# oresat-batteries-v1_1.net
KiCad netlist of a schematic drawn in EAGLE
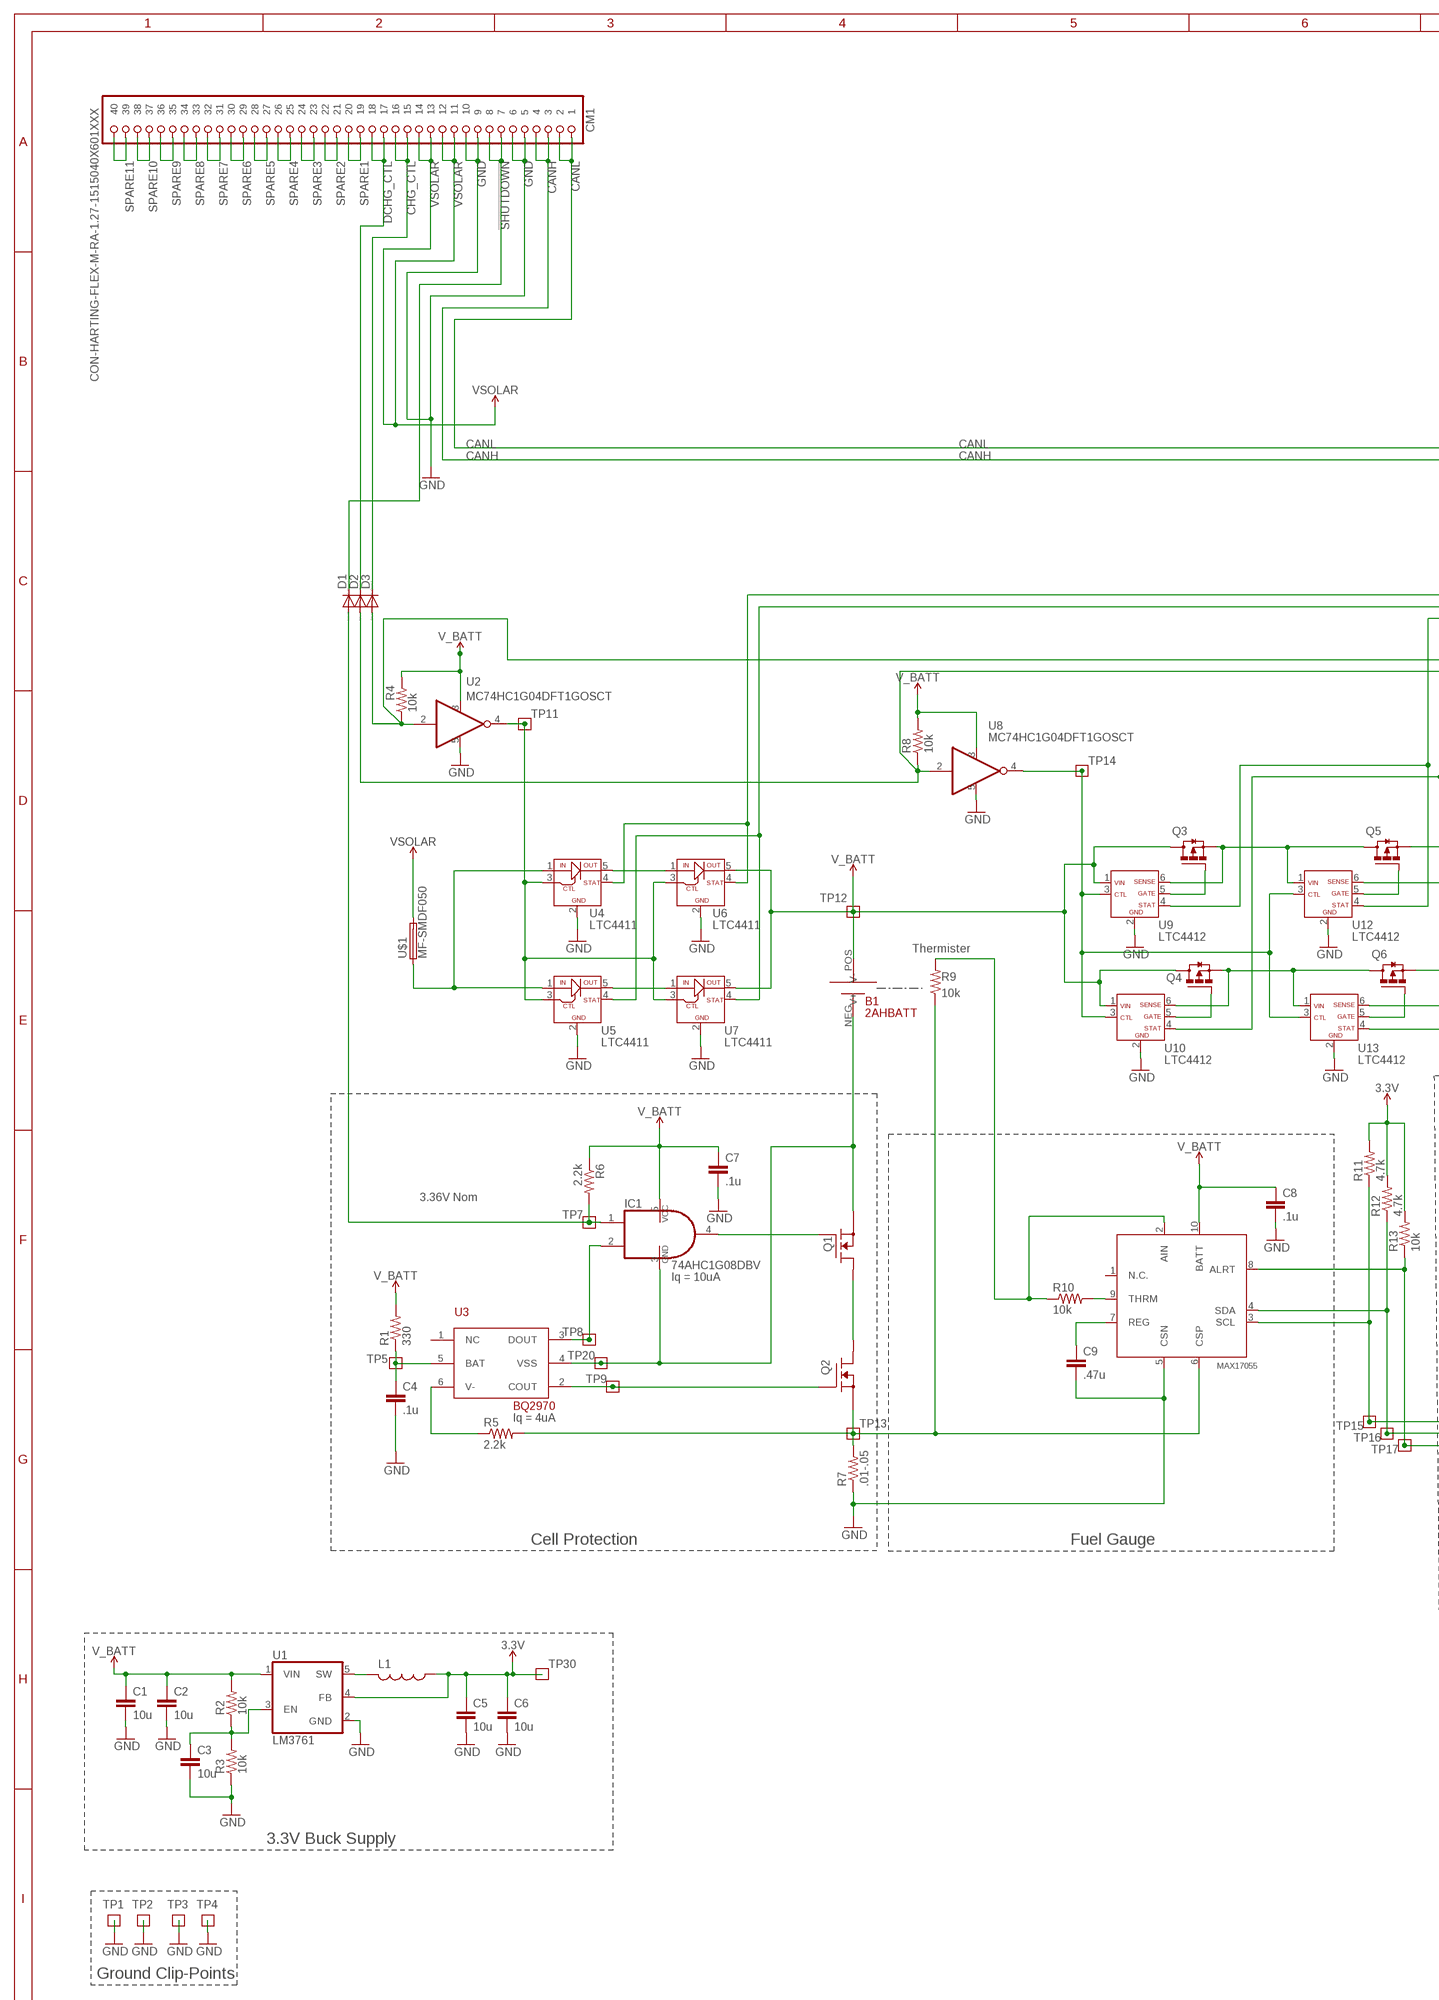
[diagram p0: schematic, sheet 1, part 1 of 2]
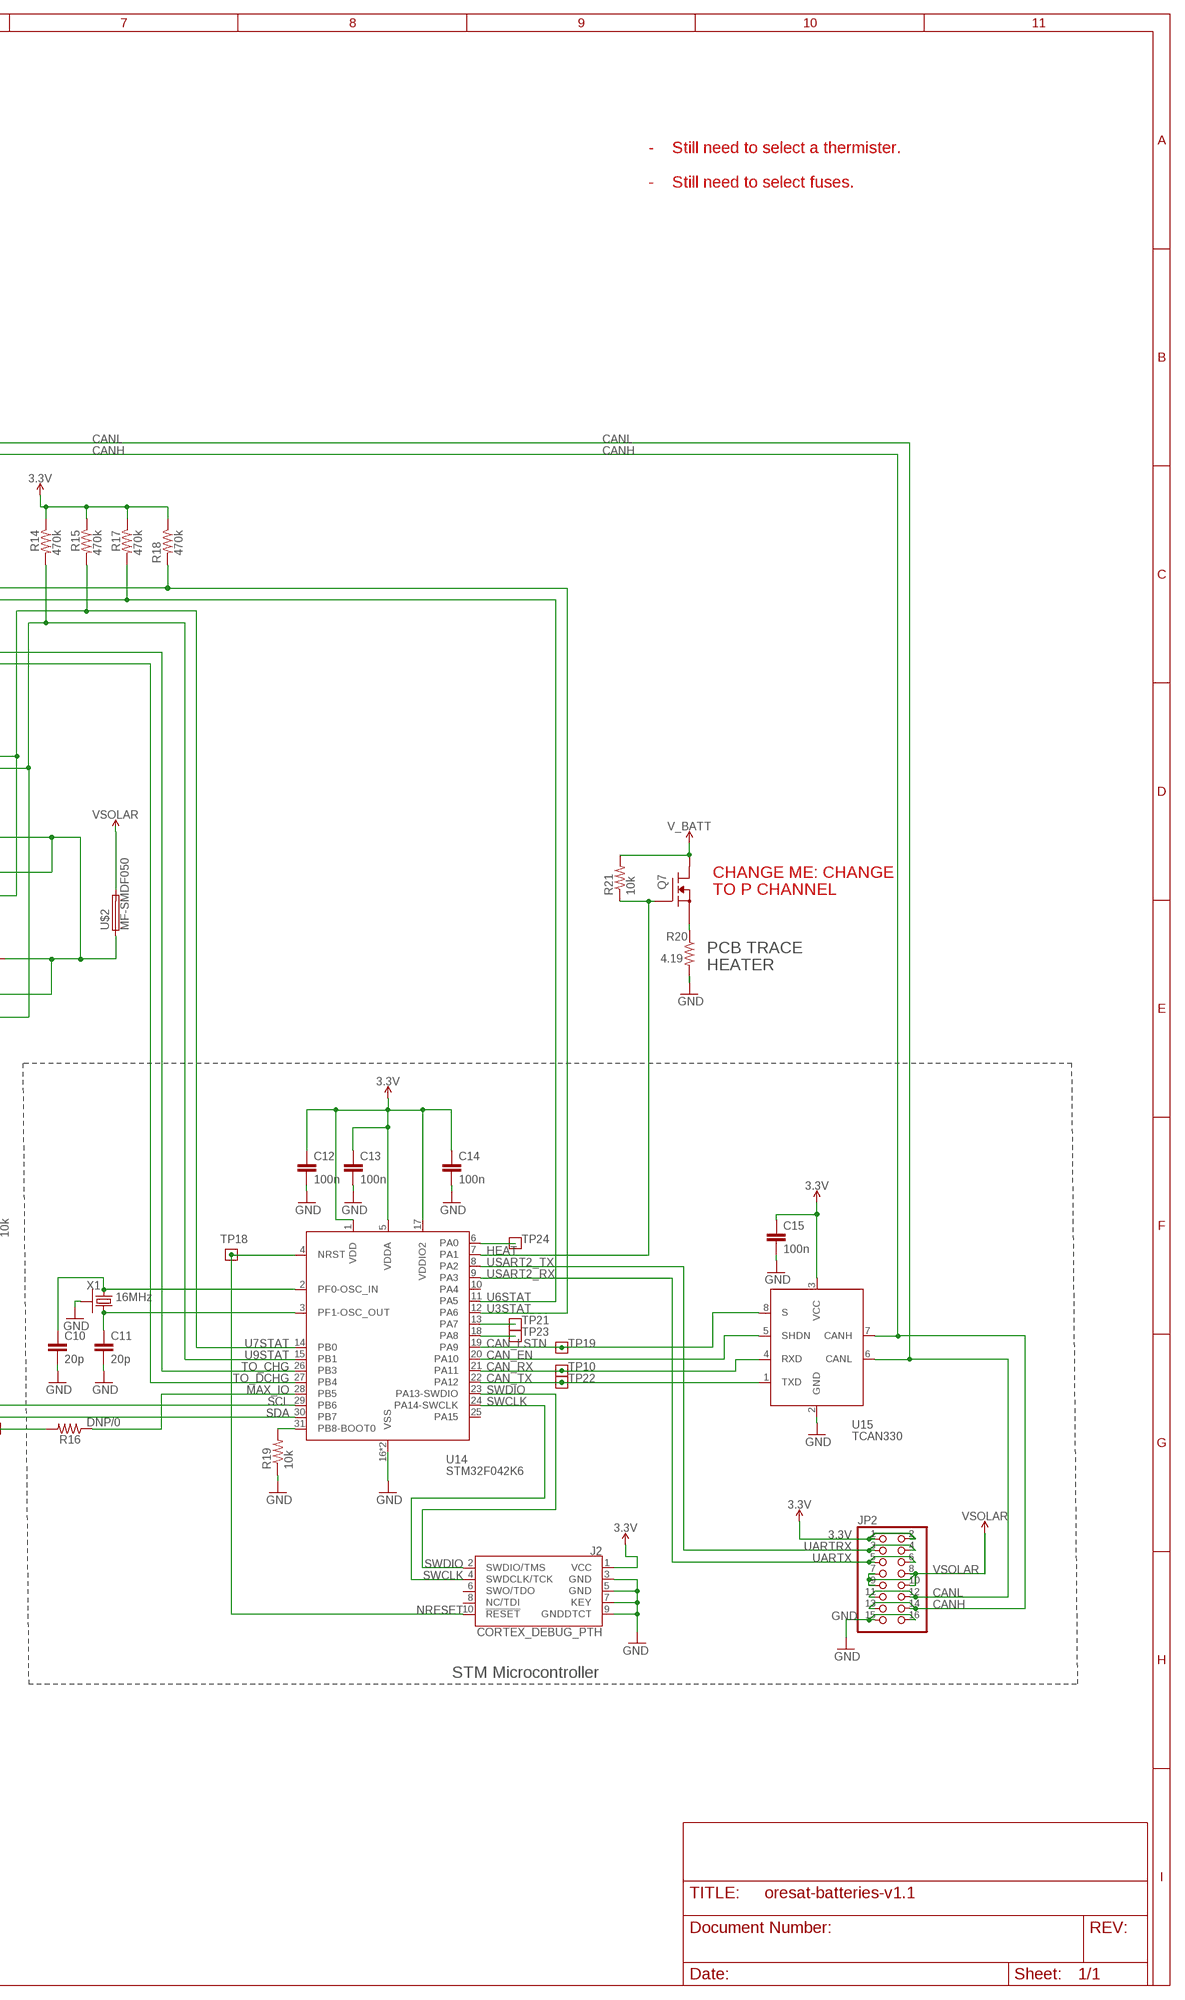
[diagram p1: schematic, sheet 1, part 2 of 2]

(export (version "E")
  (design (tool "Eeschema 10.0.6"))
  (components
    (comp (ref "B1")
      (value "2AHBATT")
      (footprint "eagle-import:2AH_605060")
      (libsource (lib "eagle-import") (part "2AHBATT"))
    )
    (comp (ref "C1")
      (value "10u")
      (footprint "eagle-import:C0805")
      (libsource (lib "eagle-import") (part "C-EUC0805"))
    )
    (comp (ref "C2")
      (value "10u")
      (footprint "eagle-import:C0805")
      (libsource (lib "eagle-import") (part "C-EUC0805"))
    )
    (comp (ref "C3")
      (value "10u")
      (footprint "eagle-import:C0805")
      (libsource (lib "eagle-import") (part "C-EUC0805"))
    )
    (comp (ref "C4")
      (value ".1u")
      (footprint "eagle-import:C0603")
      (libsource (lib "eagle-import") (part "C-EUC0603"))
    )
    (comp (ref "C5")
      (value "10u")
      (footprint "eagle-import:C0805")
      (libsource (lib "eagle-import") (part "C-EUC0805"))
    )
    (comp (ref "C6")
      (value "10u")
      (footprint "eagle-import:C0805")
      (libsource (lib "eagle-import") (part "C-EUC0805"))
    )
    (comp (ref "C7")
      (value ".1u")
      (footprint "eagle-import:C0603")
      (libsource (lib "eagle-import") (part "C-EUC0603"))
    )
    (comp (ref "C8")
      (value ".1u")
      (footprint "eagle-import:C0603")
      (libsource (lib "eagle-import") (part "C-EUC0603"))
    )
    (comp (ref "C9")
      (value ".47u")
      (footprint "eagle-import:C0603")
      (libsource (lib "eagle-import") (part "C-EUC0603"))
    )
    (comp (ref "C10")
      (value "20p")
      (footprint "eagle-import:C0603")
      (libsource (lib "eagle-import") (part "C-EUC0603"))
    )
    (comp (ref "C11")
      (value "20p")
      (footprint "eagle-import:C0603")
      (libsource (lib "eagle-import") (part "C-EUC0603"))
    )
    (comp (ref "C12")
      (value "100n")
      (footprint "eagle-import:C0603")
      (libsource (lib "eagle-import") (part "C-EUC0603"))
    )
    (comp (ref "C13")
      (value "100n")
      (footprint "eagle-import:C0603")
      (libsource (lib "eagle-import") (part "C-EUC0603"))
    )
    (comp (ref "C14")
      (value "100n")
      (footprint "eagle-import:C0603")
      (libsource (lib "eagle-import") (part "C-EUC0603"))
    )
    (comp (ref "C15")
      (value "100n")
      (footprint "eagle-import:C0603")
      (libsource (lib "eagle-import") (part "C-EUC0603"))
    )
    (comp (ref "CM1")
      (value "CON-HARTING-FLEX-M-RA-1.27-1515040X601XXX")
      (footprint "eagle-import:CON-1.27-M-RA-HARTING-1515040X601XXX")
      (libsource (lib "eagle-import") (part "CON-HARTING-FLEX-M-RA-1.27-1515040X601XXX"))
    )
    (comp (ref "D1")
      (value "CMDD6001")
      (footprint "eagle-import:SOD323")
      (libsource (lib "eagle-import") (part "CMDD6001"))
    )
    (comp (ref "D2")
      (value "CMDD6001")
      (footprint "eagle-import:SOD323")
      (libsource (lib "eagle-import") (part "CMDD6001"))
    )
    (comp (ref "D3")
      (value "CMDD6001")
      (footprint "eagle-import:SOD323")
      (libsource (lib "eagle-import") (part "CMDD6001"))
    )
    (comp (ref "IC1")
      (value "74AHC1G08DBV")
      (footprint "eagle-import:SOT23-5")
      (libsource (lib "eagle-import") (part "741G08DBVAHC"))
    )
    (comp (ref "J2")
      (value "CORTEX_DEBUG_PTH")
      (footprint "eagle-import:2X5-PTH-1.27MM")
      (libsource (lib "eagle-import") (part "CORTEX_DEBUG_PTH"))
    )
    (comp (ref "JP2")
      (value "PINHD-2X8")
      (footprint "eagle-import:2X08")
      (libsource (lib "eagle-import") (part "PINHD-2X8"))
    )
    (comp (ref "L1")
      (value "L-USL2012C")
      (footprint "eagle-import:L2012C")
      (libsource (lib "eagle-import") (part "L-USL2012C"))
    )
    (comp (ref "Q1")
      (value "CSD16340Q3")
      (footprint "eagle-import:Q3")
      (libsource (lib "eagle-import") (part "CSD16340Q3"))
    )
    (comp (ref "Q2")
      (value "CSD16340Q3")
      (footprint "eagle-import:Q3")
      (libsource (lib "eagle-import") (part "CSD16340Q3"))
    )
    (comp (ref "Q3")
      (value "TPN4R712MD")
      (footprint "eagle-import:TSON-ADVANCE-3X3")
      (libsource (lib "eagle-import") (part "TPN4R712MD"))
    )
    (comp (ref "Q4")
      (value "TPN4R712MD")
      (footprint "eagle-import:TSON-ADVANCE-3X3")
      (libsource (lib "eagle-import") (part "TPN4R712MD"))
    )
    (comp (ref "Q5")
      (value "TPN4R712MD")
      (footprint "eagle-import:TSON-ADVANCE-3X3")
      (libsource (lib "eagle-import") (part "TPN4R712MD"))
    )
    (comp (ref "Q6")
      (value "TPN4R712MD")
      (footprint "eagle-import:TSON-ADVANCE-3X3")
      (libsource (lib "eagle-import") (part "TPN4R712MD"))
    )
    (comp (ref "Q7")
      (value "CSD16340Q3")
      (footprint "eagle-import:Q3")
      (libsource (lib "eagle-import") (part "CSD16340Q3"))
    )
    (comp (ref "R1")
      (value "330")
      (footprint "eagle-import:R0603")
      (libsource (lib "eagle-import") (part "R-US_R0603"))
    )
    (comp (ref "R2")
      (value "10k")
      (footprint "eagle-import:R0603")
      (libsource (lib "eagle-import") (part "R-US_R0603"))
    )
    (comp (ref "R3")
      (value "10k")
      (footprint "eagle-import:R0603")
      (libsource (lib "eagle-import") (part "R-US_R0603"))
    )
    (comp (ref "R4")
      (value "10k")
      (footprint "eagle-import:R0603")
      (libsource (lib "eagle-import") (part "R-US_R0603"))
    )
    (comp (ref "R5")
      (value "2.2k")
      (footprint "eagle-import:R0603")
      (libsource (lib "eagle-import") (part "R-US_R0603"))
    )
    (comp (ref "R6")
      (value "2.2k")
      (footprint "eagle-import:R0603")
      (libsource (lib "eagle-import") (part "R-US_R0603"))
    )
    (comp (ref "R7")
      (value ".01-.05")
      (footprint "eagle-import:R2512")
      (libsource (lib "eagle-import") (part "R-US_R2512"))
    )
    (comp (ref "R8")
      (value "10k")
      (footprint "eagle-import:R0603")
      (libsource (lib "eagle-import") (part "R-US_R0603"))
    )
    (comp (ref "R9")
      (value "10k")
      (footprint "eagle-import:R0603")
      (libsource (lib "eagle-import") (part "R-US_R0603"))
    )
    (comp (ref "R10")
      (value "10k")
      (footprint "eagle-import:R0603")
      (libsource (lib "eagle-import") (part "R-US_R0603"))
    )
    (comp (ref "R11")
      (value "4.7k")
      (footprint "eagle-import:R0603")
      (libsource (lib "eagle-import") (part "R-US_R0603"))
    )
    (comp (ref "R12")
      (value "4.7k")
      (footprint "eagle-import:R0603")
      (libsource (lib "eagle-import") (part "R-US_R0603"))
    )
    (comp (ref "R13")
      (value "10k")
      (footprint "eagle-import:R0603")
      (libsource (lib "eagle-import") (part "R-US_R0603"))
    )
    (comp (ref "R14")
      (value "470k")
      (footprint "eagle-import:R0603")
      (libsource (lib "eagle-import") (part "R-US_R0603"))
    )
    (comp (ref "R15")
      (value "470k")
      (footprint "eagle-import:R0603")
      (libsource (lib "eagle-import") (part "R-US_R0603"))
    )
    (comp (ref "R16")
      (value "DNP/0")
      (footprint "eagle-import:R0603")
      (libsource (lib "eagle-import") (part "R-US_R0603"))
    )
    (comp (ref "R17")
      (value "470k")
      (footprint "eagle-import:R0603")
      (libsource (lib "eagle-import") (part "R-US_R0603"))
    )
    (comp (ref "R18")
      (value "470k")
      (footprint "eagle-import:R0603")
      (libsource (lib "eagle-import") (part "R-US_R0603"))
    )
    (comp (ref "R19")
      (value "10k")
      (footprint "eagle-import:R0603")
      (libsource (lib "eagle-import") (part "R-US_R0603"))
    )
    (comp (ref "R20")
      (value "4.19")
      (footprint "eagle-import:RES_HEATER")
      (libsource (lib "eagle-import") (part "RES_HEATER"))
    )
    (comp (ref "R21")
      (value "10k")
      (footprint "eagle-import:R0603")
      (libsource (lib "eagle-import") (part "R-US_R0603"))
    )
    (comp (ref "TP1")
      (value "TP")
      (footprint "eagle-import:2MM_TP")
      (libsource (lib "eagle-import") (part "TP"))
    )
    (comp (ref "TP2")
      (value "TP")
      (footprint "eagle-import:2MM_TP")
      (libsource (lib "eagle-import") (part "TP"))
    )
    (comp (ref "TP3")
      (value "TP")
      (footprint "eagle-import:2MM_TP")
      (libsource (lib "eagle-import") (part "TP"))
    )
    (comp (ref "TP4")
      (value "TP")
      (footprint "eagle-import:2MM_TP")
      (libsource (lib "eagle-import") (part "TP"))
    )
    (comp (ref "TP5")
      (value "TP")
      (footprint "eagle-import:2MM_TP")
      (libsource (lib "eagle-import") (part "TP"))
    )
    (comp (ref "TP7")
      (value "TP")
      (footprint "eagle-import:2MM_TP")
      (libsource (lib "eagle-import") (part "TP"))
    )
    (comp (ref "TP8")
      (value "TP")
      (footprint "eagle-import:2MM_TP")
      (libsource (lib "eagle-import") (part "TP"))
    )
    (comp (ref "TP9")
      (value "TP")
      (footprint "eagle-import:2MM_TP")
      (libsource (lib "eagle-import") (part "TP"))
    )
    (comp (ref "TP10")
      (value "TP")
      (footprint "eagle-import:2MM_TP")
      (libsource (lib "eagle-import") (part "TP"))
    )
    (comp (ref "TP11")
      (value "TP")
      (footprint "eagle-import:2MM_TP")
      (libsource (lib "eagle-import") (part "TP"))
    )
    (comp (ref "TP12")
      (value "TP")
      (footprint "eagle-import:2MM_TP")
      (libsource (lib "eagle-import") (part "TP"))
    )
    (comp (ref "TP13")
      (value "TP")
      (footprint "eagle-import:2MM_TP")
      (libsource (lib "eagle-import") (part "TP"))
    )
    (comp (ref "TP14")
      (value "TP")
      (footprint "eagle-import:2MM_TP")
      (libsource (lib "eagle-import") (part "TP"))
    )
    (comp (ref "TP15")
      (value "TP")
      (footprint "eagle-import:2MM_TP")
      (libsource (lib "eagle-import") (part "TP"))
    )
    (comp (ref "TP16")
      (value "TP")
      (footprint "eagle-import:2MM_TP")
      (libsource (lib "eagle-import") (part "TP"))
    )
    (comp (ref "TP17")
      (value "TP")
      (footprint "eagle-import:2MM_TP")
      (libsource (lib "eagle-import") (part "TP"))
    )
    (comp (ref "TP18")
      (value "TP")
      (footprint "eagle-import:2MM_TP")
      (libsource (lib "eagle-import") (part "TP"))
    )
    (comp (ref "TP19")
      (value "TP")
      (footprint "eagle-import:2MM_TP")
      (libsource (lib "eagle-import") (part "TP"))
    )
    (comp (ref "TP20")
      (value "TP")
      (footprint "eagle-import:2MM_TP")
      (libsource (lib "eagle-import") (part "TP"))
    )
    (comp (ref "TP21")
      (value "TP")
      (footprint "eagle-import:2MM_TP")
      (libsource (lib "eagle-import") (part "TP"))
    )
    (comp (ref "TP22")
      (value "TP")
      (footprint "eagle-import:2MM_TP")
      (libsource (lib "eagle-import") (part "TP"))
    )
    (comp (ref "TP23")
      (value "TP")
      (footprint "eagle-import:2MM_TP")
      (libsource (lib "eagle-import") (part "TP"))
    )
    (comp (ref "TP24")
      (value "TP")
      (footprint "eagle-import:2MM_TP")
      (libsource (lib "eagle-import") (part "TP"))
    )
    (comp (ref "TP30")
      (value "TP")
      (footprint "eagle-import:2MM_TP")
      (libsource (lib "eagle-import") (part "TP"))
    )
    (comp (ref "U$1")
      (value "MF-SMDF050")
      (footprint "eagle-import:MF-SMDF050")
      (libsource (lib "eagle-import") (part "MF-SMDF050"))
    )
    (comp (ref "U$2")
      (value "MF-SMDF050")
      (footprint "eagle-import:MF-SMDF050")
      (libsource (lib "eagle-import") (part "MF-SMDF050"))
    )
    (comp (ref "U1")
      (value "LM3761")
      (footprint "eagle-import:SOT23-5")
      (libsource (lib "eagle-import") (part "LM3761"))
    )
    (comp (ref "U2")
      (value "MC74HC1G04DFT1GOSCT")
      (footprint "eagle-import:SC70-5")
      (libsource (lib "eagle-import") (part "MC74HC1G04DFT1GOSCT"))
    )
    (comp (ref "U3")
      (value "BQ2970")
      (footprint "eagle-import:PSOP6")
      (libsource (lib "eagle-import") (part "BQ2970"))
    )
    (comp (ref "U4")
      (value "LTC4411")
      (footprint "eagle-import:SOT23-5-B")
      (libsource (lib "eagle-import") (part "LTC4411"))
    )
    (comp (ref "U5")
      (value "LTC4411")
      (footprint "eagle-import:SOT23-5-B")
      (libsource (lib "eagle-import") (part "LTC4411"))
    )
    (comp (ref "U6")
      (value "LTC4411")
      (footprint "eagle-import:SOT23-5-B")
      (libsource (lib "eagle-import") (part "LTC4411"))
    )
    (comp (ref "U7")
      (value "LTC4411")
      (footprint "eagle-import:SOT23-5-B")
      (libsource (lib "eagle-import") (part "LTC4411"))
    )
    (comp (ref "U8")
      (value "MC74HC1G04DFT1GOSCT")
      (footprint "eagle-import:SC70-5")
      (libsource (lib "eagle-import") (part "MC74HC1G04DFT1GOSCT"))
    )
    (comp (ref "U9")
      (value "LTC4412")
      (footprint "eagle-import:SOT23-6")
      (libsource (lib "eagle-import") (part "LTC4412"))
    )
    (comp (ref "U10")
      (value "LTC4412")
      (footprint "eagle-import:SOT23-6")
      (libsource (lib "eagle-import") (part "LTC4412"))
    )
    (comp (ref "U11")
      (value "MAX17055")
      (footprint "eagle-import:TDFN-10L")
      (libsource (lib "eagle-import") (part "MAX17055"))
    )
    (comp (ref "U12")
      (value "LTC4412")
      (footprint "eagle-import:SOT23-6")
      (libsource (lib "eagle-import") (part "LTC4412"))
    )
    (comp (ref "U13")
      (value "LTC4412")
      (footprint "eagle-import:SOT23-6")
      (libsource (lib "eagle-import") (part "LTC4412"))
    )
    (comp (ref "U14")
      (value "STM32F042K6")
      (footprint "eagle-import:QFP32-7X7")
      (libsource (lib "eagle-import") (part "STM32F042K6"))
    )
    (comp (ref "U15")
      (value "TCAN330")
      (footprint "eagle-import:SOT23-8_TI-DCN")
      (libsource (lib "eagle-import") (part "TCAN330"))
    )
    (comp (ref "X1")
      (value "16MHz")
      (footprint "eagle-import:CRYSTAL_2.5X2")
      (libsource (lib "eagle-import") (part "CRYSTAL-WITH-GND"))
    )
  )
  (nets
    (net (code "1") (name "/CANH") (class "Default")
      (node (ref "CM1") (pin "3") (pinfunction "3_3") (pintype "passive"))
      (node (ref "CM1") (pin "4") (pinfunction "4_4") (pintype "passive"))
      (node (ref "JP2") (pin "13") (pinfunction "13_13") (pintype "passive"))
      (node (ref "JP2") (pin "14") (pinfunction "14_14") (pintype "passive"))
      (node (ref "U15") (pin "7") (pinfunction "CANH_7") (pintype "bidirectional"))
    )
    (net (code "2") (name "/CANL") (class "Default")
      (node (ref "CM1") (pin "1") (pinfunction "1_1") (pintype "passive"))
      (node (ref "CM1") (pin "2") (pinfunction "2_2") (pintype "passive"))
      (node (ref "JP2") (pin "11") (pinfunction "11_11") (pintype "passive"))
      (node (ref "JP2") (pin "12") (pinfunction "12_12") (pintype "passive"))
      (node (ref "U15") (pin "6") (pinfunction "CANL_6") (pintype "bidirectional"))
    )
    (net (code "3") (name "/CHG_CTL") (class "Default")
      (node (ref "CM1") (pin "15") (pinfunction "15_15") (pintype "passive"))
      (node (ref "CM1") (pin "16") (pinfunction "16_16") (pintype "passive"))
      (node (ref "D3") (pin "1") (pinfunction "C_1") (pintype "passive"))
    )
    (net (code "4") (name "/DCHG_CTL") (class "Default")
      (node (ref "CM1") (pin "17") (pinfunction "17_17") (pintype "passive"))
      (node (ref "CM1") (pin "18") (pinfunction "18_18") (pintype "passive"))
      (node (ref "D2") (pin "1") (pinfunction "C_1") (pintype "passive"))
    )
    (net (code "5") (name "/MAX_IO") (class "Default")
      (node (ref "R16") (pin "1") (pinfunction "1_1") (pintype "passive"))
      (node (ref "U14") (pin "28") (pinfunction "PB5_28") (pintype "bidirectional"))
    )
    (net (code "6") (name "/NRESET") (class "Default")
      (node (ref "J2") (pin "10") (pinfunction "~{RESET}_10") (pintype "bidirectional"))
      (node (ref "TP18") (pin "P$1") (pinfunction "P$1_P$1") (pintype "passive"))
      (node (ref "U14") (pin "4") (pinfunction "NRST_4") (pintype "bidirectional"))
    )
    (net (code "7") (name "/SPARE1") (class "Default")
      (node (ref "CM1") (pin "19") (pinfunction "19_19") (pintype "passive"))
      (node (ref "CM1") (pin "20") (pinfunction "20_20") (pintype "passive"))
    )
    (net (code "8") (name "/SPARE2") (class "Default")
      (node (ref "CM1") (pin "21") (pinfunction "21_21") (pintype "passive"))
      (node (ref "CM1") (pin "22") (pinfunction "22_22") (pintype "passive"))
    )
    (net (code "9") (name "/SPARE3") (class "Default")
      (node (ref "CM1") (pin "23") (pinfunction "23_23") (pintype "passive"))
      (node (ref "CM1") (pin "24") (pinfunction "24_24") (pintype "passive"))
    )
    (net (code "10") (name "/SPARE4") (class "Default")
      (node (ref "CM1") (pin "25") (pinfunction "25_25") (pintype "passive"))
      (node (ref "CM1") (pin "26") (pinfunction "26_26") (pintype "passive"))
    )
    (net (code "11") (name "/SPARE5") (class "Default")
      (node (ref "CM1") (pin "27") (pinfunction "27_27") (pintype "passive"))
      (node (ref "CM1") (pin "28") (pinfunction "28_28") (pintype "passive"))
    )
    (net (code "12") (name "/SPARE6") (class "Default")
      (node (ref "CM1") (pin "29") (pinfunction "29_29") (pintype "passive"))
      (node (ref "CM1") (pin "30") (pinfunction "30_30") (pintype "passive"))
    )
    (net (code "13") (name "/SPARE7") (class "Default")
      (node (ref "CM1") (pin "31") (pinfunction "31_31") (pintype "passive"))
      (node (ref "CM1") (pin "32") (pinfunction "32_32") (pintype "passive"))
    )
    (net (code "14") (name "/SPARE8") (class "Default")
      (node (ref "CM1") (pin "33") (pinfunction "33_33") (pintype "passive"))
      (node (ref "CM1") (pin "34") (pinfunction "34_34") (pintype "passive"))
    )
    (net (code "15") (name "/SPARE9") (class "Default")
      (node (ref "CM1") (pin "35") (pinfunction "35_35") (pintype "passive"))
      (node (ref "CM1") (pin "36") (pinfunction "36_36") (pintype "passive"))
    )
    (net (code "16") (name "/SPARE10") (class "Default")
      (node (ref "CM1") (pin "37") (pinfunction "37_37") (pintype "passive"))
      (node (ref "CM1") (pin "38") (pinfunction "38_38") (pintype "passive"))
    )
    (net (code "17") (name "/SPARE11") (class "Default")
      (node (ref "CM1") (pin "39") (pinfunction "39_39") (pintype "passive"))
      (node (ref "CM1") (pin "40") (pinfunction "40_40") (pintype "passive"))
    )
    (net (code "18") (name "/SWCLK") (class "Default")
      (node (ref "J2") (pin "4") (pinfunction "SWDCLK/TCK_4") (pintype "bidirectional"))
      (node (ref "U14") (pin "24") (pinfunction "PA14-SWCLK_24") (pintype "bidirectional"))
    )
    (net (code "19") (name "/SWDIO") (class "Default")
      (node (ref "J2") (pin "2") (pinfunction "SWDIO/TMS_2") (pintype "bidirectional"))
      (node (ref "U14") (pin "23") (pinfunction "PA13-SWDIO_23") (pintype "bidirectional"))
    )
    (net (code "20") (name "/TO_CHG") (class "Default")
      (node (ref "D3") (pin "2") (pinfunction "A_2") (pintype "passive"))
      (node (ref "R4") (pin "1") (pinfunction "1_1") (pintype "passive"))
      (node (ref "U14") (pin "26") (pinfunction "PB3_26") (pintype "bidirectional"))
      (node (ref "U2") (pin "2") (pinfunction "INA_2") (pintype "input"))
    )
    (net (code "21") (name "/TO_DCHG") (class "Default")
      (node (ref "D2") (pin "2") (pinfunction "A_2") (pintype "passive"))
      (node (ref "R8") (pin "1") (pinfunction "1_1") (pintype "passive"))
      (node (ref "U14") (pin "27") (pinfunction "PB4_27") (pintype "bidirectional"))
      (node (ref "U8") (pin "2") (pinfunction "INA_2") (pintype "input"))
    )
    (net (code "22") (name "/U3STAT") (class "Default")
      (node (ref "R18") (pin "2") (pinfunction "2_2") (pintype "passive"))
      (node (ref "U14") (pin "12") (pinfunction "PA6_12") (pintype "bidirectional"))
      (node (ref "U4") (pin "4") (pinfunction "STAT_4") (pintype "open_collector"))
      (node (ref "U6") (pin "4") (pinfunction "STAT_4") (pintype "open_collector"))
    )
    (net (code "23") (name "/U6STAT") (class "Default")
      (node (ref "R17") (pin "2") (pinfunction "2_2") (pintype "passive"))
      (node (ref "U14") (pin "11") (pinfunction "PA5_11") (pintype "bidirectional"))
      (node (ref "U5") (pin "4") (pinfunction "STAT_4") (pintype "open_collector"))
      (node (ref "U7") (pin "4") (pinfunction "STAT_4") (pintype "open_collector"))
    )
    (net (code "24") (name "/U7STAT") (class "Default")
      (node (ref "R15") (pin "2") (pinfunction "2_2") (pintype "passive"))
      (node (ref "U12") (pin "4") (pinfunction "STAT_4") (pintype "open_collector"))
      (node (ref "U14") (pin "14") (pinfunction "PB0_14") (pintype "bidirectional"))
      (node (ref "U9") (pin "4") (pinfunction "STAT_4") (pintype "open_collector"))
    )
    (net (code "25") (name "/U9STAT") (class "Default")
      (node (ref "R14") (pin "2") (pinfunction "2_2") (pintype "passive"))
      (node (ref "U10") (pin "4") (pinfunction "STAT_4") (pintype "open_collector"))
      (node (ref "U13") (pin "4") (pinfunction "STAT_4") (pintype "open_collector"))
      (node (ref "U14") (pin "15") (pinfunction "PB1_15") (pintype "bidirectional"))
    )
    (net (code "26") (name "/~{SHUTDOWN}") (class "Default")
      (node (ref "CM1") (pin "7") (pinfunction "7_7") (pintype "passive"))
      (node (ref "CM1") (pin "8") (pinfunction "8_8") (pintype "passive"))
      (node (ref "D1") (pin "1") (pinfunction "C_1") (pintype "passive"))
    )
    (net (code "27") (name "3.3V") (class "Default")
      (node (ref "C12") (pin "1") (pinfunction "1_1") (pintype "passive"))
      (node (ref "C13") (pin "1") (pinfunction "1_1") (pintype "passive"))
      (node (ref "C14") (pin "1") (pinfunction "1_1") (pintype "passive"))
      (node (ref "C15") (pin "1") (pinfunction "1_1") (pintype "passive"))
      (node (ref "C5") (pin "1") (pinfunction "1_1") (pintype "passive"))
      (node (ref "C6") (pin "1") (pinfunction "1_1") (pintype "passive"))
      (node (ref "J2") (pin "1") (pinfunction "VCC_1") (pintype "bidirectional"))
      (node (ref "JP2") (pin "1") (pinfunction "1_1") (pintype "passive"))
      (node (ref "JP2") (pin "2") (pinfunction "2_2") (pintype "passive"))
      (node (ref "L1") (pin "1") (pinfunction "1_1") (pintype "passive"))
      (node (ref "R11") (pin "2") (pinfunction "2_2") (pintype "passive"))
      (node (ref "R12") (pin "2") (pinfunction "2_2") (pintype "passive"))
      (node (ref "R13") (pin "2") (pinfunction "2_2") (pintype "passive"))
      (node (ref "R14") (pin "1") (pinfunction "1_1") (pintype "passive"))
      (node (ref "R15") (pin "1") (pinfunction "1_1") (pintype "passive"))
      (node (ref "R17") (pin "1") (pinfunction "1_1") (pintype "passive"))
      (node (ref "R18") (pin "1") (pinfunction "1_1") (pintype "passive"))
      (node (ref "TP30") (pin "P$1") (pinfunction "P$1_P$1") (pintype "passive"))
      (node (ref "U1") (pin "4") (pinfunction "FB_4") (pintype "input"))
      (node (ref "U14") (pin "1") (pinfunction "VDD_1") (pintype "power_in"))
      (node (ref "U14") (pin "17") (pinfunction "VDDIO2_17") (pintype "power_in"))
      (node (ref "U14") (pin "5") (pinfunction "VDDA_5") (pintype "power_in"))
      (node (ref "U15") (pin "3") (pinfunction "VCC_3") (pintype "power_in"))
    )
    (net (code "28") (name "GND") (class "Default")
      (node (ref "C1") (pin "2") (pinfunction "2_2") (pintype "passive"))
      (node (ref "C10") (pin "2") (pinfunction "2_2") (pintype "passive"))
      (node (ref "C11") (pin "2") (pinfunction "2_2") (pintype "passive"))
      (node (ref "C12") (pin "2") (pinfunction "2_2") (pintype "passive"))
      (node (ref "C13") (pin "2") (pinfunction "2_2") (pintype "passive"))
      (node (ref "C14") (pin "2") (pinfunction "2_2") (pintype "passive"))
      (node (ref "C15") (pin "2") (pinfunction "2_2") (pintype "passive"))
      (node (ref "C2") (pin "2") (pinfunction "2_2") (pintype "passive"))
      (node (ref "C3") (pin "2") (pinfunction "2_2") (pintype "passive"))
      (node (ref "C4") (pin "2") (pinfunction "2_2") (pintype "passive"))
      (node (ref "C5") (pin "2") (pinfunction "2_2") (pintype "passive"))
      (node (ref "C6") (pin "2") (pinfunction "2_2") (pintype "passive"))
      (node (ref "C7") (pin "2") (pinfunction "2_2") (pintype "passive"))
      (node (ref "C8") (pin "2") (pinfunction "2_2") (pintype "passive"))
      (node (ref "C9") (pin "2") (pinfunction "2_2") (pintype "passive"))
      (node (ref "CM1") (pin "10") (pinfunction "10_10") (pintype "passive"))
      (node (ref "CM1") (pin "5") (pinfunction "5_5") (pintype "passive"))
      (node (ref "CM1") (pin "6") (pinfunction "6_6") (pintype "passive"))
      (node (ref "CM1") (pin "9") (pinfunction "9_9") (pintype "passive"))
      (node (ref "J2") (pin "3") (pinfunction "GND_3") (pintype "bidirectional"))
      (node (ref "J2") (pin "5") (pinfunction "GND_5") (pintype "bidirectional"))
      (node (ref "J2") (pin "7") (pinfunction "KEY_7") (pintype "bidirectional"))
      (node (ref "J2") (pin "9") (pinfunction "GNDDTCT_9") (pintype "bidirectional"))
      (node (ref "JP2") (pin "15") (pinfunction "15_15") (pintype "passive"))
      (node (ref "JP2") (pin "16") (pinfunction "16_16") (pintype "passive"))
      (node (ref "R19") (pin "1") (pinfunction "1_1") (pintype "passive"))
      (node (ref "R20") (pin "V-") (pinfunction "2_V-") (pintype "passive"))
      (node (ref "R3") (pin "1") (pinfunction "1_1") (pintype "passive"))
      (node (ref "R7") (pin "1") (pinfunction "1_1") (pintype "passive"))
      (node (ref "TP1") (pin "P$1") (pinfunction "P$1_P$1") (pintype "passive"))
      (node (ref "TP2") (pin "P$1") (pinfunction "P$1_P$1") (pintype "passive"))
      (node (ref "TP3") (pin "P$1") (pinfunction "P$1_P$1") (pintype "passive"))
      (node (ref "TP4") (pin "P$1") (pinfunction "P$1_P$1") (pintype "passive"))
      (node (ref "U1") (pin "2") (pinfunction "GND_2") (pintype "bidirectional"))
      (node (ref "U10") (pin "2") (pinfunction "GND_2") (pintype "power_in"))
      (node (ref "U11") (pin "5") (pinfunction "CSN_5") (pintype "bidirectional"))
      (node (ref "U12") (pin "2") (pinfunction "GND_2") (pintype "power_in"))
      (node (ref "U13") (pin "2") (pinfunction "GND_2") (pintype "power_in"))
      (node (ref "U14") (pin "16") (pinfunction "VSS_16") (pintype "power_in"))
      (node (ref "U14") (pin "32") (pinfunction "VSS_32") (pintype "power_in"))
      (node (ref "U15") (pin "2") (pinfunction "GND_2") (pintype "power_in"))
      (node (ref "U2") (pin "5") (pinfunction "GND_5") (pintype "bidirectional"))
      (node (ref "U4") (pin "2") (pinfunction "GND_2") (pintype "power_in"))
      (node (ref "U5") (pin "2") (pinfunction "GND_2") (pintype "power_in"))
      (node (ref "U6") (pin "2") (pinfunction "GND_2") (pintype "power_in"))
      (node (ref "U7") (pin "2") (pinfunction "GND_2") (pintype "power_in"))
      (node (ref "U8") (pin "5") (pinfunction "GND_5") (pintype "bidirectional"))
      (node (ref "U9") (pin "2") (pinfunction "GND_2") (pintype "power_in"))
      (node (ref "X1") (pin "2") (pinfunction "SHIELD_2") (pintype "power_in"))
      (node (ref "X1") (pin "4") (pinfunction "SHIELD_4") (pintype "power_in"))
    )
    (net (code "29") (name "Net-(B1-V-)") (class "Default")
      (node (ref "B1") (pin "NEG") (pinfunction "V-_NEG") (pintype "bidirectional"))
      (node (ref "IC1") (pin "3") (pinfunction "GND_3") (pintype "power_in"))
      (node (ref "Q1") (pin "P$1") (pinfunction "S_P$1") (pintype "passive"))
      (node (ref "Q1") (pin "P$2") (pinfunction "S_P$2") (pintype "passive"))
      (node (ref "Q1") (pin "P$3") (pinfunction "S_P$3") (pintype "passive"))
      (node (ref "TP20") (pin "P$1") (pinfunction "P$1_P$1") (pintype "passive"))
      (node (ref "U3") (pin "4") (pinfunction "VSS_4") (pintype "bidirectional"))
    )
    (net (code "30") (name "Net-(D1-A)") (class "Default")
      (node (ref "D1") (pin "2") (pinfunction "A_2") (pintype "passive"))
      (node (ref "IC1") (pin "1") (pinfunction "I0_1") (pintype "input"))
      (node (ref "R6") (pin "2") (pinfunction "2_2") (pintype "passive"))
      (node (ref "TP7") (pin "P$1") (pinfunction "P$1_P$1") (pintype "passive"))
    )
    (net (code "31") (name "Net-(IC1A-I1)") (class "Default")
      (node (ref "IC1") (pin "2") (pinfunction "I1_2") (pintype "input"))
      (node (ref "TP8") (pin "P$1") (pinfunction "P$1_P$1") (pintype "passive"))
      (node (ref "U3") (pin "3") (pinfunction "DOUT_3") (pintype "bidirectional"))
    )
    (net (code "32") (name "Net-(IC1A-O)") (class "Default")
      (node (ref "IC1") (pin "4") (pinfunction "O_4") (pintype "output"))
      (node (ref "Q1") (pin "P$4") (pinfunction "G_P$4") (pintype "passive"))
    )
    (net (code "33") (name "Net-(Q1-D-PadP$5)") (class "Default")
      (node (ref "Q1") (pin "P$5") (pinfunction "D_P$5") (pintype "passive"))
      (node (ref "Q1") (pin "P$6") (pinfunction "D_P$6") (pintype "passive"))
      (node (ref "Q1") (pin "P$7") (pinfunction "D_P$7") (pintype "passive"))
      (node (ref "Q1") (pin "P$8") (pinfunction "D_P$8") (pintype "passive"))
      (node (ref "Q1") (pin "P$9") (pinfunction "D_P$9") (pintype "passive"))
      (node (ref "Q2") (pin "P$5") (pinfunction "D_P$5") (pintype "passive"))
      (node (ref "Q2") (pin "P$6") (pinfunction "D_P$6") (pintype "passive"))
      (node (ref "Q2") (pin "P$7") (pinfunction "D_P$7") (pintype "passive"))
      (node (ref "Q2") (pin "P$8") (pinfunction "D_P$8") (pintype "passive"))
      (node (ref "Q2") (pin "P$9") (pinfunction "D_P$9") (pintype "passive"))
    )
    (net (code "34") (name "Net-(Q2-G)") (class "Default")
      (node (ref "Q2") (pin "P$4") (pinfunction "G_P$4") (pintype "passive"))
      (node (ref "TP9") (pin "P$1") (pinfunction "P$1_P$1") (pintype "passive"))
      (node (ref "U3") (pin "2") (pinfunction "COUT_2") (pintype "bidirectional"))
    )
    (net (code "35") (name "Net-(Q3-G)") (class "Default")
      (node (ref "Q3") (pin "4") (pinfunction "G_4") (pintype "passive"))
      (node (ref "U9") (pin "5") (pinfunction "GATE_5") (pintype "output"))
    )
    (net (code "36") (name "Net-(Q4-G)") (class "Default")
      (node (ref "Q4") (pin "4") (pinfunction "G_4") (pintype "passive"))
      (node (ref "U10") (pin "5") (pinfunction "GATE_5") (pintype "output"))
    )
    (net (code "37") (name "Net-(Q5-G)") (class "Default")
      (node (ref "Q5") (pin "4") (pinfunction "G_4") (pintype "passive"))
      (node (ref "U12") (pin "5") (pinfunction "GATE_5") (pintype "output"))
    )
    (net (code "38") (name "Net-(Q6-G)") (class "Default")
      (node (ref "Q6") (pin "4") (pinfunction "G_4") (pintype "passive"))
      (node (ref "U13") (pin "5") (pinfunction "GATE_5") (pintype "output"))
    )
    (net (code "39") (name "Net-(Q7-G)") (class "Default")
      (node (ref "Q7") (pin "P$4") (pinfunction "G_P$4") (pintype "passive"))
      (node (ref "R21") (pin "1") (pinfunction "1_1") (pintype "passive"))
      (node (ref "U14") (pin "7") (pinfunction "PA1_7") (pintype "bidirectional"))
    )
    (net (code "40") (name "Net-(R20-1)") (class "Default")
      (node (ref "Q7") (pin "P$1") (pinfunction "S_P$1") (pintype "passive"))
      (node (ref "Q7") (pin "P$2") (pinfunction "S_P$2") (pintype "passive"))
      (node (ref "Q7") (pin "P$3") (pinfunction "S_P$3") (pintype "passive"))
      (node (ref "R20") (pin "V+") (pinfunction "1_V+") (pintype "passive"))
    )
    (net (code "41") (name "Net-(U1-EN)") (class "Default")
      (node (ref "C3") (pin "1") (pinfunction "1_1") (pintype "passive"))
      (node (ref "R2") (pin "1") (pinfunction "1_1") (pintype "passive"))
      (node (ref "R3") (pin "2") (pinfunction "2_2") (pintype "passive"))
      (node (ref "U1") (pin "3") (pinfunction "EN_3") (pintype "input"))
    )
    (net (code "42") (name "Net-(U1-SW)") (class "Default")
      (node (ref "L1") (pin "2") (pinfunction "2_2") (pintype "passive"))
      (node (ref "U1") (pin "5") (pinfunction "SW_5") (pintype "bidirectional"))
    )
    (net (code "43") (name "Net-(U2-OUT)") (class "Default")
      (node (ref "TP11") (pin "P$1") (pinfunction "P$1_P$1") (pintype "passive"))
      (node (ref "U2") (pin "4") (pinfunction "OUT_4") (pintype "output"))
      (node (ref "U4") (pin "3") (pinfunction "CTL_3") (pintype "input"))
      (node (ref "U5") (pin "3") (pinfunction "CTL_3") (pintype "input"))
      (node (ref "U6") (pin "3") (pinfunction "CTL_3") (pintype "input"))
      (node (ref "U7") (pin "3") (pinfunction "CTL_3") (pintype "input"))
    )
    (net (code "44") (name "Net-(U3-BAT)") (class "Default")
      (node (ref "C4") (pin "1") (pinfunction "1_1") (pintype "passive"))
      (node (ref "R1") (pin "1") (pinfunction "1_1") (pintype "passive"))
      (node (ref "TP5") (pin "P$1") (pinfunction "P$1_P$1") (pintype "passive"))
      (node (ref "U3") (pin "5") (pinfunction "BAT_5") (pintype "bidirectional"))
    )
    (net (code "45") (name "Net-(U3-V-)") (class "Default")
      (node (ref "R5") (pin "1") (pinfunction "1_1") (pintype "passive"))
      (node (ref "U3") (pin "6") (pinfunction "V-_6") (pintype "bidirectional"))
    )
    (net (code "46") (name "Net-(U4-IN)") (class "Default")
      (node (ref "U$1") (pin "1") (pinfunction "1_1") (pintype "passive"))
      (node (ref "U4") (pin "1") (pinfunction "IN_1") (pintype "power_in"))
      (node (ref "U5") (pin "1") (pinfunction "IN_1") (pintype "power_in"))
    )
    (net (code "47") (name "Net-(U4-OUT)") (class "Default")
      (node (ref "U4") (pin "5") (pinfunction "OUT_5") (pintype "power_in"))
      (node (ref "U6") (pin "1") (pinfunction "IN_1") (pintype "power_in"))
    )
    (net (code "48") (name "Net-(U5-OUT)") (class "Default")
      (node (ref "U5") (pin "5") (pinfunction "OUT_5") (pintype "power_in"))
      (node (ref "U7") (pin "1") (pinfunction "IN_1") (pintype "power_in"))
    )
    (net (code "49") (name "Net-(U10-CTL)") (class "Default")
      (node (ref "TP14") (pin "P$1") (pinfunction "P$1_P$1") (pintype "passive"))
      (node (ref "U10") (pin "3") (pinfunction "CTL_3") (pintype "input"))
      (node (ref "U12") (pin "3") (pinfunction "CTL_3") (pintype "input"))
      (node (ref "U13") (pin "3") (pinfunction "CTL_3") (pintype "input"))
      (node (ref "U8") (pin "4") (pinfunction "OUT_4") (pintype "output"))
      (node (ref "U9") (pin "3") (pinfunction "CTL_3") (pintype "input"))
    )
    (net (code "50") (name "Net-(U10-SENSE)") (class "Default")
      (node (ref "Q4") (pin "1") (pinfunction "S_1") (pintype "passive"))
      (node (ref "Q4") (pin "2") (pinfunction "S_2") (pintype "passive"))
      (node (ref "Q4") (pin "3") (pinfunction "S_3") (pintype "passive"))
      (node (ref "Q6") (pin "5") (pinfunction "D_5") (pintype "passive"))
      (node (ref "Q6") (pin "6") (pinfunction "D_6") (pintype "passive"))
      (node (ref "Q6") (pin "7") (pinfunction "D_7") (pintype "passive"))
      (node (ref "Q6") (pin "8") (pinfunction "D_8") (pintype "passive"))
      (node (ref "U10") (pin "6") (pinfunction "SENSE_6") (pintype "input"))
      (node (ref "U13") (pin "1") (pinfunction "VIN_1") (pintype "power_in"))
    )
    (net (code "51") (name "Net-(U11-AIN)") (class "Default")
      (node (ref "R10") (pin "1") (pinfunction "1_1") (pintype "passive"))
      (node (ref "R9") (pin "2") (pinfunction "2_2") (pintype "passive"))
      (node (ref "U11") (pin "2") (pinfunction "AIN_2") (pintype "bidirectional"))
    )
    (net (code "52") (name "Net-(U11-ALRT)") (class "Default")
      (node (ref "R13") (pin "1") (pinfunction "1_1") (pintype "passive"))
      (node (ref "R16") (pin "2") (pinfunction "2_2") (pintype "passive"))
      (node (ref "TP17") (pin "P$1") (pinfunction "P$1_P$1") (pintype "passive"))
      (node (ref "U11") (pin "8") (pinfunction "ALRT_8") (pintype "bidirectional"))
    )
    (net (code "53") (name "Net-(U11-CSP)") (class "Default")
      (node (ref "Q2") (pin "P$1") (pinfunction "S_P$1") (pintype "passive"))
      (node (ref "Q2") (pin "P$2") (pinfunction "S_P$2") (pintype "passive"))
      (node (ref "Q2") (pin "P$3") (pinfunction "S_P$3") (pintype "passive"))
      (node (ref "R5") (pin "2") (pinfunction "2_2") (pintype "passive"))
      (node (ref "R7") (pin "2") (pinfunction "2_2") (pintype "passive"))
      (node (ref "R9") (pin "1") (pinfunction "1_1") (pintype "passive"))
      (node (ref "TP13") (pin "P$1") (pinfunction "P$1_P$1") (pintype "passive"))
      (node (ref "U11") (pin "6") (pinfunction "CSP_6") (pintype "bidirectional"))
    )
    (net (code "54") (name "Net-(U11-REG)") (class "Default")
      (node (ref "C9") (pin "1") (pinfunction "1_1") (pintype "passive"))
      (node (ref "U11") (pin "7") (pinfunction "REG_7") (pintype "bidirectional"))
    )
    (net (code "55") (name "Net-(U11-SCL)") (class "Default")
      (node (ref "R11") (pin "1") (pinfunction "1_1") (pintype "passive"))
      (node (ref "TP15") (pin "P$1") (pinfunction "P$1_P$1") (pintype "passive"))
      (node (ref "U11") (pin "3") (pinfunction "SCL_3") (pintype "bidirectional"))
      (node (ref "U14") (pin "29") (pinfunction "PB6_29") (pintype "bidirectional"))
    )
    (net (code "56") (name "Net-(U11-SDA)") (class "Default")
      (node (ref "R12") (pin "1") (pinfunction "1_1") (pintype "passive"))
      (node (ref "TP16") (pin "P$1") (pinfunction "P$1_P$1") (pintype "passive"))
      (node (ref "U11") (pin "4") (pinfunction "SDA_4") (pintype "bidirectional"))
      (node (ref "U14") (pin "30") (pinfunction "PB7_30") (pintype "bidirectional"))
    )
    (net (code "57") (name "Net-(U11-THRM)") (class "Default")
      (node (ref "R10") (pin "2") (pinfunction "2_2") (pintype "passive"))
      (node (ref "U11") (pin "9") (pinfunction "THRM_9") (pintype "bidirectional"))
    )
    (net (code "58") (name "Net-(U12-SENSE)") (class "Default")
      (node (ref "Q5") (pin "1") (pinfunction "S_1") (pintype "passive"))
      (node (ref "Q5") (pin "2") (pinfunction "S_2") (pintype "passive"))
      (node (ref "Q5") (pin "3") (pinfunction "S_3") (pintype "passive"))
      (node (ref "Q6") (pin "1") (pinfunction "S_1") (pintype "passive"))
      (node (ref "Q6") (pin "2") (pinfunction "S_2") (pintype "passive"))
      (node (ref "Q6") (pin "3") (pinfunction "S_3") (pintype "passive"))
      (node (ref "U$2") (pin "1") (pinfunction "1_1") (pintype "passive"))
      (node (ref "U12") (pin "6") (pinfunction "SENSE_6") (pintype "input"))
      (node (ref "U13") (pin "6") (pinfunction "SENSE_6") (pintype "input"))
    )
    (net (code "59") (name "Net-(U12-VIN)") (class "Default")
      (node (ref "Q3") (pin "1") (pinfunction "S_1") (pintype "passive"))
      (node (ref "Q3") (pin "2") (pinfunction "S_2") (pintype "passive"))
      (node (ref "Q3") (pin "3") (pinfunction "S_3") (pintype "passive"))
      (node (ref "Q5") (pin "5") (pinfunction "D_5") (pintype "passive"))
      (node (ref "Q5") (pin "6") (pinfunction "D_6") (pintype "passive"))
      (node (ref "Q5") (pin "7") (pinfunction "D_7") (pintype "passive"))
      (node (ref "Q5") (pin "8") (pinfunction "D_8") (pintype "passive"))
      (node (ref "U12") (pin "1") (pinfunction "VIN_1") (pintype "power_in"))
      (node (ref "U9") (pin "6") (pinfunction "SENSE_6") (pintype "input"))
    )
    (net (code "60") (name "Net-(U14-PA0)") (class "Default")
      (node (ref "TP24") (pin "P$1") (pinfunction "P$1_P$1") (pintype "passive"))
      (node (ref "U14") (pin "6") (pinfunction "PA0_6") (pintype "bidirectional"))
    )
    (net (code "61") (name "Net-(U14-PA2)") (class "Default")
      (node (ref "JP2") (pin "3") (pinfunction "3_3") (pintype "passive"))
      (node (ref "JP2") (pin "4") (pinfunction "4_4") (pintype "passive"))
      (node (ref "U14") (pin "8") (pinfunction "PA2_8") (pintype "bidirectional"))
    )
    (net (code "62") (name "Net-(U14-PA3)") (class "Default")
      (node (ref "JP2") (pin "5") (pinfunction "5_5") (pintype "passive"))
      (node (ref "JP2") (pin "6") (pinfunction "6_6") (pintype "passive"))
      (node (ref "U14") (pin "9") (pinfunction "PA3_9") (pintype "bidirectional"))
    )
    (net (code "63") (name "Net-(U14-PA7)") (class "Default")
      (node (ref "TP21") (pin "P$1") (pinfunction "P$1_P$1") (pintype "passive"))
      (node (ref "U14") (pin "13") (pinfunction "PA7_13") (pintype "bidirectional"))
    )
    (net (code "64") (name "Net-(U14-PA8)") (class "Default")
      (node (ref "TP23") (pin "P$1") (pinfunction "P$1_P$1") (pintype "passive"))
      (node (ref "U14") (pin "18") (pinfunction "PA8_18") (pintype "bidirectional"))
    )
    (net (code "65") (name "Net-(U14-PA9)") (class "Default")
      (node (ref "TP19") (pin "P$1") (pinfunction "P$1_P$1") (pintype "passive"))
      (node (ref "U14") (pin "19") (pinfunction "PA9_19") (pintype "bidirectional"))
      (node (ref "U15") (pin "8") (pinfunction "S_8") (pintype "input"))
    )
    (net (code "66") (name "Net-(U14-PA10)") (class "Default")
      (node (ref "U14") (pin "20") (pinfunction "PA10_20") (pintype "bidirectional"))
      (node (ref "U15") (pin "5") (pinfunction "SHDN_5") (pintype "input"))
    )
    (net (code "67") (name "Net-(U14-PA11)") (class "Default")
      (node (ref "TP10") (pin "P$1") (pinfunction "P$1_P$1") (pintype "passive"))
      (node (ref "U14") (pin "21") (pinfunction "PA11_21") (pintype "bidirectional"))
      (node (ref "U15") (pin "4") (pinfunction "RXD_4") (pintype "output"))
    )
    (net (code "68") (name "Net-(U14-PA12)") (class "Default")
      (node (ref "TP22") (pin "P$1") (pinfunction "P$1_P$1") (pintype "passive"))
      (node (ref "U14") (pin "22") (pinfunction "PA12_22") (pintype "bidirectional"))
      (node (ref "U15") (pin "1") (pinfunction "TXD_1") (pintype "input"))
    )
    (net (code "69") (name "Net-(U14-PB8-BOOT0)") (class "Default")
      (node (ref "R19") (pin "2") (pinfunction "2_2") (pintype "passive"))
      (node (ref "U14") (pin "31") (pinfunction "PB8-BOOT0_31") (pintype "bidirectional"))
    )
    (net (code "70") (name "Net-(U14-PF0-OSC_IN)") (class "Default")
      (node (ref "C10") (pin "1") (pinfunction "1_1") (pintype "passive"))
      (node (ref "U14") (pin "2") (pinfunction "PF0-OSC_IN_2") (pintype "bidirectional"))
      (node (ref "X1") (pin "1") (pinfunction "1_1") (pintype "passive"))
    )
    (net (code "71") (name "Net-(U14-PF1-OSC_OUT)") (class "Default")
      (node (ref "C11") (pin "1") (pinfunction "1_1") (pintype "passive"))
      (node (ref "U14") (pin "3") (pinfunction "PF1-OSC_OUT_3") (pintype "bidirectional"))
      (node (ref "X1") (pin "3") (pinfunction "2_3") (pintype "passive"))
    )
    (net (code "72") (name "VSOLAR") (class "Default")
      (node (ref "CM1") (pin "11") (pinfunction "11_11") (pintype "passive"))
      (node (ref "CM1") (pin "12") (pinfunction "12_12") (pintype "passive"))
      (node (ref "CM1") (pin "13") (pinfunction "13_13") (pintype "passive"))
      (node (ref "CM1") (pin "14") (pinfunction "14_14") (pintype "passive"))
      (node (ref "JP2") (pin "10") (pinfunction "10_10") (pintype "passive"))
      (node (ref "JP2") (pin "7") (pinfunction "7_7") (pintype "passive"))
      (node (ref "JP2") (pin "8") (pinfunction "8_8") (pintype "passive"))
      (node (ref "JP2") (pin "9") (pinfunction "9_9") (pintype "passive"))
      (node (ref "U$1") (pin "2") (pinfunction "2_2") (pintype "passive"))
      (node (ref "U$2") (pin "2") (pinfunction "2_2") (pintype "passive"))
    )
    (net (code "73") (name "V_BATT") (class "Default")
      (node (ref "B1") (pin "POS") (pinfunction "V+_POS") (pintype "bidirectional"))
      (node (ref "C1") (pin "1") (pinfunction "1_1") (pintype "passive"))
      (node (ref "C2") (pin "1") (pinfunction "1_1") (pintype "passive"))
      (node (ref "C7") (pin "1") (pinfunction "1_1") (pintype "passive"))
      (node (ref "C8") (pin "1") (pinfunction "1_1") (pintype "passive"))
      (node (ref "IC1") (pin "5") (pinfunction "VCC_5") (pintype "power_in"))
      (node (ref "Q3") (pin "5") (pinfunction "D_5") (pintype "passive"))
      (node (ref "Q3") (pin "6") (pinfunction "D_6") (pintype "passive"))
      (node (ref "Q3") (pin "7") (pinfunction "D_7") (pintype "passive"))
      (node (ref "Q3") (pin "8") (pinfunction "D_8") (pintype "passive"))
      (node (ref "Q4") (pin "5") (pinfunction "D_5") (pintype "passive"))
      (node (ref "Q4") (pin "6") (pinfunction "D_6") (pintype "passive"))
      (node (ref "Q4") (pin "7") (pinfunction "D_7") (pintype "passive"))
      (node (ref "Q4") (pin "8") (pinfunction "D_8") (pintype "passive"))
      (node (ref "Q7") (pin "P$5") (pinfunction "D_P$5") (pintype "passive"))
      (node (ref "Q7") (pin "P$6") (pinfunction "D_P$6") (pintype "passive"))
      (node (ref "Q7") (pin "P$7") (pinfunction "D_P$7") (pintype "passive"))
      (node (ref "Q7") (pin "P$8") (pinfunction "D_P$8") (pintype "passive"))
      (node (ref "Q7") (pin "P$9") (pinfunction "D_P$9") (pintype "passive"))
      (node (ref "R1") (pin "2") (pinfunction "2_2") (pintype "passive"))
      (node (ref "R2") (pin "2") (pinfunction "2_2") (pintype "passive"))
      (node (ref "R21") (pin "2") (pinfunction "2_2") (pintype "passive"))
      (node (ref "R4") (pin "2") (pinfunction "2_2") (pintype "passive"))
      (node (ref "R6") (pin "1") (pinfunction "1_1") (pintype "passive"))
      (node (ref "R8") (pin "2") (pinfunction "2_2") (pintype "passive"))
      (node (ref "TP12") (pin "P$1") (pinfunction "P$1_P$1") (pintype "passive"))
      (node (ref "U1") (pin "1") (pinfunction "VIN_1") (pintype "bidirectional"))
      (node (ref "U10") (pin "1") (pinfunction "VIN_1") (pintype "power_in"))
      (node (ref "U11") (pin "10") (pinfunction "BATT_10") (pintype "bidirectional"))
      (node (ref "U2") (pin "3") (pinfunction "VCC_3") (pintype "bidirectional"))
      (node (ref "U6") (pin "5") (pinfunction "OUT_5") (pintype "power_in"))
      (node (ref "U7") (pin "5") (pinfunction "OUT_5") (pintype "power_in"))
      (node (ref "U8") (pin "3") (pinfunction "VCC_3") (pintype "bidirectional"))
      (node (ref "U9") (pin "1") (pinfunction "VIN_1") (pintype "power_in"))
    )
    (net (code "74") (name "unconnected-(J2-NC{slash}TDI-Pad8)") (class "Default")
      (node (ref "J2") (pin "8") (pinfunction "NC/TDI_8") (pintype "bidirectional"))
    )
    (net (code "75") (name "unconnected-(J2-SWO{slash}TDO-Pad6)") (class "Default")
      (node (ref "J2") (pin "6") (pinfunction "SWO/TDO_6") (pintype "bidirectional"))
    )
    (net (code "76") (name "unconnected-(U3-NC-Pad1)") (class "Default")
      (node (ref "U3") (pin "1") (pinfunction "NC_1") (pintype "bidirectional"))
    )
    (net (code "77") (name "unconnected-(U11-N.C.-Pad1)") (class "Default")
      (node (ref "U11") (pin "1") (pinfunction "N.C._1") (pintype "bidirectional"))
    )
    (net (code "78") (name "unconnected-(U14-PA4-Pad10)") (class "Default")
      (node (ref "U14") (pin "10") (pinfunction "PA4_10") (pintype "bidirectional"))
    )
    (net (code "79") (name "unconnected-(U14-PA15-Pad25)") (class "Default")
      (node (ref "U14") (pin "25") (pinfunction "PA15_25") (pintype "bidirectional"))
    )
  )
)
